# controller_board.net
KiCad netlist of a schematic drawn in EAGLE
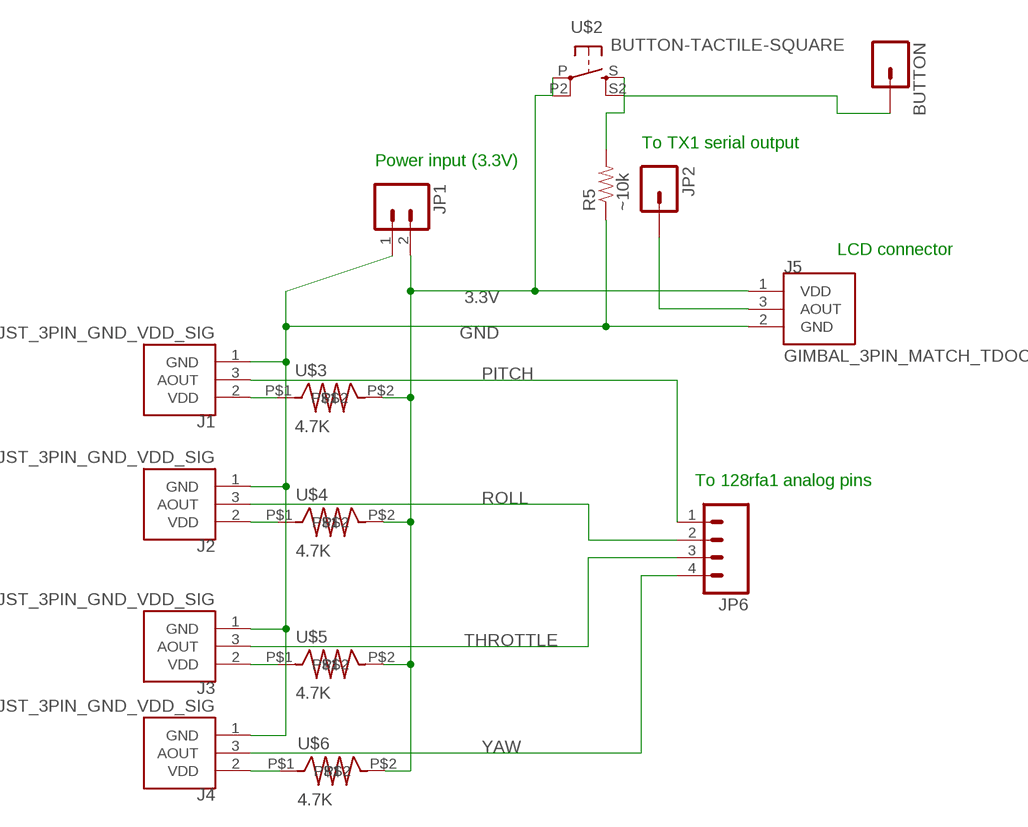
[diagram p0: schematic, sheet 1]

(export (version "E")
  (design (tool "Eeschema 10.0.6"))
  (components
    (comp (ref "BUTTON")
      (value "M01PTH")
      (footprint "eagle-import:1X01")
      (libsource (lib "eagle-import") (part "M01PTH"))
    )
    (comp (ref "J1")
      (value "JST_3PIN_GND_VDD_SIG")
      (footprint "eagle-import:JST-3-PTH-REVERSE")
      (libsource (lib "eagle-import") (part "JST_3PIN_GND_VDD_SIG"))
    )
    (comp (ref "J2")
      (value "JST_3PIN_GND_VDD_SIG")
      (footprint "eagle-import:JST-3-PTH-REVERSE")
      (libsource (lib "eagle-import") (part "JST_3PIN_GND_VDD_SIG"))
    )
    (comp (ref "J3")
      (value "JST_3PIN_GND_VDD_SIG")
      (footprint "eagle-import:JST-3-PTH-REVERSE")
      (libsource (lib "eagle-import") (part "JST_3PIN_GND_VDD_SIG"))
    )
    (comp (ref "J4")
      (value "JST_3PIN_GND_VDD_SIG")
      (footprint "eagle-import:JST-3-PTH-REVERSE")
      (libsource (lib "eagle-import") (part "JST_3PIN_GND_VDD_SIG"))
    )
    (comp (ref "J5")
      (value "GIMBAL_3PIN_MATCH_TDOCU")
      (footprint "eagle-import:JST-3-PTH")
      (libsource (lib "eagle-import") (part "GIMBAL_3PIN_MATCH_TDOCU"))
    )
    (comp (ref "JP1")
      (value "M021X02_NO_SILK")
      (footprint "eagle-import:1X02_NO_SILK")
      (libsource (lib "eagle-import") (part "M021X02_NO_SILK"))
    )
    (comp (ref "JP2")
      (value "M01PTH")
      (footprint "eagle-import:1X01")
      (libsource (lib "eagle-import") (part "M01PTH"))
    )
    (comp (ref "JP6")
      (value "M04PTH")
      (footprint "eagle-import:1X04")
      (libsource (lib "eagle-import") (part "M04PTH"))
    )
    (comp (ref "R5")
      (value "~10k")
      (footprint "eagle-import:AXIAL-0.4")
      (libsource (lib "eagle-import") (part "RESISTORPTH-1/4W"))
    )
    (comp (ref "U$2")
      (value "BUTTON-TACTILE-SQUARE")
      (footprint "eagle-import:BUTTON-TACTILE-SQUARE-ADAFRUIT1010")
      (libsource (lib "eagle-import") (part "BUTTON-TACTILE-SQUARE"))
    )
    (comp (ref "U$3")
      (value "4.7K")
      (footprint "eagle-import:CRF12_RESISTOR")
      (fields (field (name "CREATOR") "David Smith"))
      (libsource (lib "eagle-import") (part "CRF12_RESISTOR"))
    )
    (comp (ref "U$4")
      (value "4.7K")
      (footprint "eagle-import:CRF12_RESISTOR")
      (fields (field (name "CREATOR") "David Smith"))
      (libsource (lib "eagle-import") (part "CRF12_RESISTOR"))
    )
    (comp (ref "U$5")
      (value "4.7K")
      (footprint "eagle-import:CRF12_RESISTOR")
      (fields (field (name "CREATOR") "David Smith"))
      (libsource (lib "eagle-import") (part "CRF12_RESISTOR"))
    )
    (comp (ref "U$6")
      (value "4.7K")
      (footprint "eagle-import:CRF12_RESISTOR")
      (fields (field (name "CREATOR") "David Smith"))
      (libsource (lib "eagle-import") (part "CRF12_RESISTOR"))
    )
  )
  (nets
    (net (code "1") (name "/3.3V") (class "Default")
      (node (ref "J5") (pin "1") (pinfunction "VDD_1") (pintype "power_in"))
      (node (ref "JP1") (pin "2") (pinfunction "2_2") (pintype "passive"))
      (node (ref "U$2") (pin "P") (pinfunction "P_P") (pintype "passive"))
      (node (ref "U$2") (pin "P2") (pinfunction "P1_P2") (pintype "passive"))
      (node (ref "U$3") (pin "P$2") (pinfunction "P$2_P$2") (pintype "bidirectional"))
      (node (ref "U$4") (pin "P$2") (pinfunction "P$2_P$2") (pintype "bidirectional"))
      (node (ref "U$5") (pin "P$2") (pinfunction "P$2_P$2") (pintype "bidirectional"))
      (node (ref "U$6") (pin "P$2") (pinfunction "P$2_P$2") (pintype "bidirectional"))
    )
    (net (code "2") (name "/GND") (class "Default")
      (node (ref "J1") (pin "1") (pinfunction "GND_1") (pintype "power_in"))
      (node (ref "J2") (pin "1") (pinfunction "GND_1") (pintype "power_in"))
      (node (ref "J3") (pin "1") (pinfunction "GND_1") (pintype "power_in"))
      (node (ref "J4") (pin "1") (pinfunction "GND_1") (pintype "power_in"))
      (node (ref "J5") (pin "2") (pinfunction "GND_2") (pintype "power_in"))
      (node (ref "JP1") (pin "1") (pinfunction "1_1") (pintype "passive"))
      (node (ref "R5") (pin "P$1") (pinfunction "1_P$1") (pintype "passive"))
    )
    (net (code "3") (name "/PITCH") (class "Default")
      (node (ref "J1") (pin "3") (pinfunction "AOUT_3") (pintype "bidirectional"))
      (node (ref "JP6") (pin "1") (pinfunction "1_1") (pintype "passive"))
    )
    (net (code "4") (name "/ROLL") (class "Default")
      (node (ref "J2") (pin "3") (pinfunction "AOUT_3") (pintype "bidirectional"))
      (node (ref "JP6") (pin "2") (pinfunction "2_2") (pintype "passive"))
    )
    (net (code "5") (name "/THROTTLE") (class "Default")
      (node (ref "J3") (pin "3") (pinfunction "AOUT_3") (pintype "bidirectional"))
      (node (ref "JP6") (pin "3") (pinfunction "3_3") (pintype "passive"))
    )
    (net (code "6") (name "/YAW") (class "Default")
      (node (ref "J4") (pin "3") (pinfunction "AOUT_3") (pintype "bidirectional"))
      (node (ref "JP6") (pin "4") (pinfunction "4_4") (pintype "passive"))
    )
    (net (code "7") (name "Net-(J1-VDD)") (class "Default")
      (node (ref "J1") (pin "2") (pinfunction "VDD_2") (pintype "power_in"))
      (node (ref "U$3") (pin "P$1") (pinfunction "P$1_P$1") (pintype "bidirectional"))
    )
    (net (code "8") (name "Net-(J2-VDD)") (class "Default")
      (node (ref "J2") (pin "2") (pinfunction "VDD_2") (pintype "power_in"))
      (node (ref "U$4") (pin "P$1") (pinfunction "P$1_P$1") (pintype "bidirectional"))
    )
    (net (code "9") (name "Net-(J3-VDD)") (class "Default")
      (node (ref "J3") (pin "2") (pinfunction "VDD_2") (pintype "power_in"))
      (node (ref "U$5") (pin "P$1") (pinfunction "P$1_P$1") (pintype "bidirectional"))
    )
    (net (code "10") (name "Net-(J4-VDD)") (class "Default")
      (node (ref "J4") (pin "2") (pinfunction "VDD_2") (pintype "power_in"))
      (node (ref "U$6") (pin "P$1") (pinfunction "P$1_P$1") (pintype "bidirectional"))
    )
    (net (code "11") (name "Net-(J5-AOUT)") (class "Default")
      (node (ref "J5") (pin "3") (pinfunction "AOUT_3") (pintype "bidirectional"))
      (node (ref "JP2") (pin "1") (pinfunction "1_1") (pintype "passive"))
    )
    (net (code "12") (name "Net-(R5-2)") (class "Default")
      (node (ref "BUTTON") (pin "1") (pinfunction "1_1") (pintype "passive"))
      (node (ref "R5") (pin "P$2") (pinfunction "2_P$2") (pintype "passive"))
      (node (ref "U$2") (pin "S") (pinfunction "S_S") (pintype "passive"))
      (node (ref "U$2") (pin "S2") (pinfunction "S1_S2") (pintype "passive"))
    )
  )
)
